# Oscar_MainBoard_Flash.net
KiCad netlist of a schematic drawn in Altium Designer
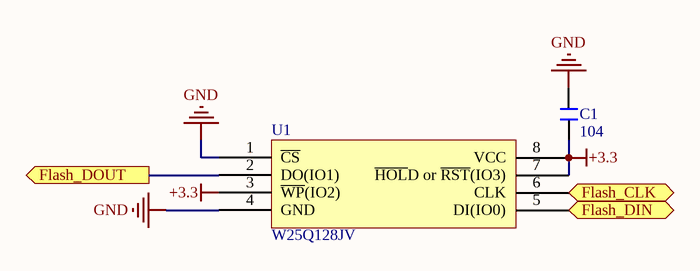
[diagram p0: Oscar_MainBoard_Flash.SchDoc]

(export (version "E")
  (design (tool "Eeschema 10.0.6"))
  (components
    (comp (ref "C1")
      (value "104")
      (footprint "C 0402_L")
      (description "贴片电容")
      (libsource (lib "0.1 - 电阻-电容-电感") (part "C"))
    )
    (comp (ref "U1")
      (value "W25Q128JV")
      (footprint "WSON-8_5X6MM")
      (description "128Mbit")
      (libsource (lib "2.0 - FLASH存储器") (part "W25Q128JV"))
    )
  )
  (nets
    (net (code "1") (name "+3.3") (class "Default")
      (node (ref "C1") (pin "1") (pinfunction "1_1") (pintype "passive"))
      (node (ref "U1") (pin "3") (pinfunction "~{WP}(IO2)_3") (pintype "passive"))
      (node (ref "U1") (pin "7") (pinfunction "~{HOL}D_or_~{RST}(IO3)_7") (pintype "passive"))
      (node (ref "U1") (pin "8") (pinfunction "VCC_8") (pintype "passive"))
    )
    (net (code "2") (name "/Flash_CLK") (class "Default")
      (node (ref "U1") (pin "6") (pinfunction "CLK_6") (pintype "passive"))
    )
    (net (code "3") (name "/Flash_DIN") (class "Default")
      (node (ref "U1") (pin "5") (pinfunction "DI(IO0)_5") (pintype "passive"))
    )
    (net (code "4") (name "/Flash_DOUT") (class "Default")
      (node (ref "U1") (pin "2") (pinfunction "DO(IO1)_2") (pintype "passive"))
    )
    (net (code "5") (name "GND") (class "Default")
      (node (ref "C1") (pin "2") (pinfunction "2_2") (pintype "passive"))
      (node (ref "U1") (pin "1") (pinfunction "~{CS}_1") (pintype "passive"))
      (node (ref "U1") (pin "4") (pinfunction "GND_4") (pintype "passive"))
    )
  )
)
